# SH4_-_3_3V_LINEAR_REGULATOR.net
KiCad netlist of a schematic drawn in Altium Designer
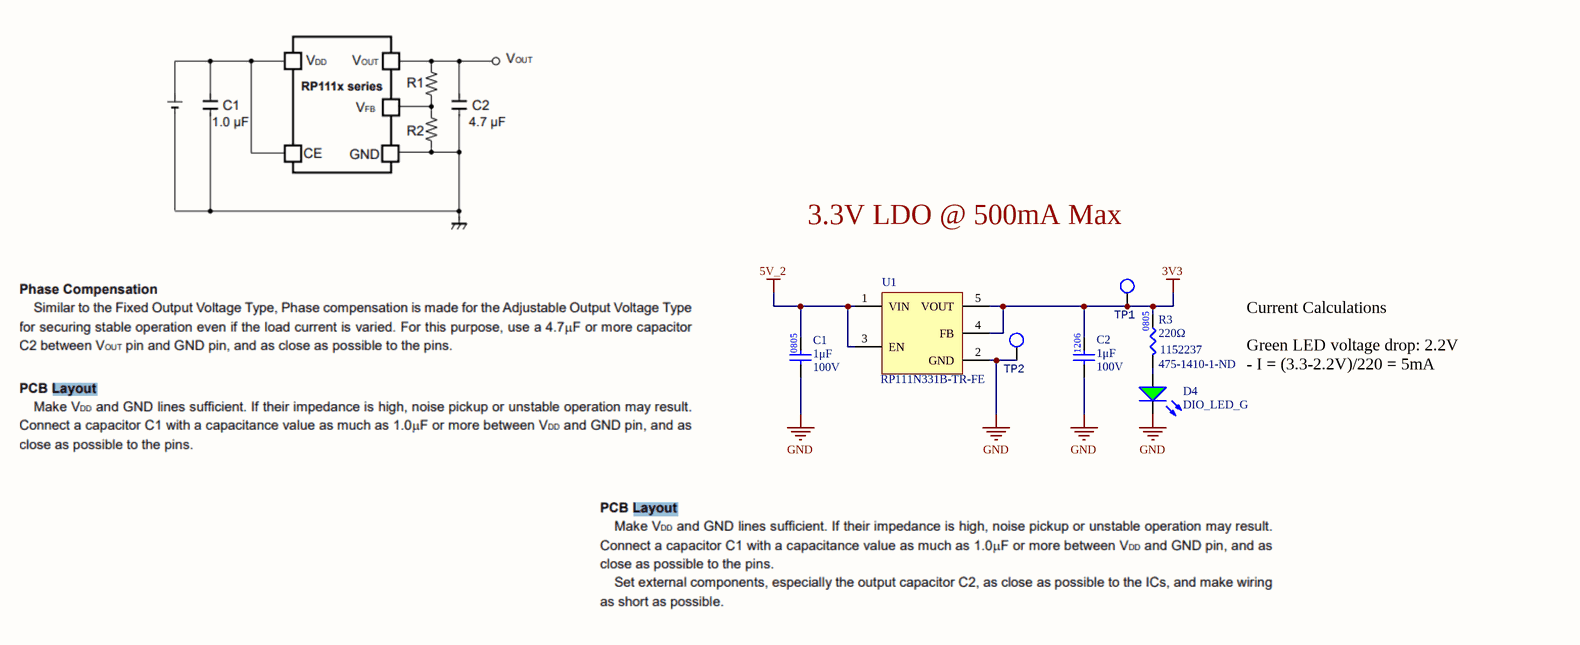
[diagram p0: SH4 - 3.3V LINEAR REGULATOR.SchDoc]

(export (version "E")
  (design (tool "Eeschema 10.0.6"))
  (components
    (comp (ref "C1")
      (value "1μF")
      (footprint "CAP0805")
      (description "CAP CER 1UF 100V X7S 0805")
      (fields (field (name "VOLTAGE RATING") "100V") (field (name "Comment") "CAP_1uF_100V_0805"))
      (libsource (lib "UWRT_Schematic_Library_2020") (part "CAP_1uF_100V_0805"))
    )
    (comp (ref "C2")
      (value "1μF")
      (footprint "CAPC3216X190X50NL20T25")
      (description "CAP CER 1UF 100V X7R 1206")
      (fields (field (name "VOLTAGE RATING") "100V") (field (name "Comment") "CAP_1uF_100V_1206"))
      (libsource (lib "UWRT_Schematic_Library_2020") (part "CAP_1uF_100V_1206"))
    )
    (comp (ref "D4")
      (value "DIO_LED_G")
      (footprint "LED_0805_GREEN")
      (description "LED GREEN DIFFUSED 0805 SMD")
      (fields
        (field (name "SUPPLIER PART NUMBER 1") "475-1410-1-ND")
        (field (name "SUPPLIER PART NUMBER 2") "1152237")
      )
      (libsource (lib "UWRT_Schematic_Library_2020") (part "DIO_LED_G"))
    )
    (comp (ref "R3")
      (value "220Ω")
      (footprint "RES0805")
      (description "RES 220 OHM 5% 1/2W 0805")
      (fields (field (name "LCSC PART #") "C17557") (field (name "Comment") "RES_220Ω_0805_5%"))
      (libsource (lib "UWRT_Schematic_Library_2020") (part "RES_220Ω_0805_5%"))
    )
    (comp (ref "TP1")
      (value "TESTPOINT_LOOP")
      (footprint "TESTPOINT_LOOP")
      (description "TESTPOINT THRUHOLE")
      (libsource (lib "UWRT_Schematic_Library_2020") (part "TESTPOINT_LOOP"))
    )
    (comp (ref "TP2")
      (value "TESTPOINT_LOOP")
      (footprint "TESTPOINT_LOOP")
      (description "TESTPOINT THRUHOLE")
      (libsource (lib "UWRT_Schematic_Library_2020") (part "TESTPOINT_LOOP"))
    )
    (comp (ref "U1")
      (value "LDO_3.3V_500mA")
      (footprint "SOT23-5")
      (description "IC REG LINEAR 3.3V 500MA SOT23-5")
      (fields (field (name "MANUFACTURER PART NUMBER 1") "RP111N331B-TR-FE"))
      (libsource (lib "UWRT_Schematic_Library_2020") (part "LDO_3.3V_500mA"))
    )
  )
  (nets
    (net (code "1") (name "3V3") (class "Default")
      (node (ref "C2") (pin "2") (pinfunction "2_2") (pintype "passive"))
      (node (ref "R3") (pin "2") (pinfunction "2_2") (pintype "passive"))
      (node (ref "TP1") (pin "1") (pintype "passive"))
      (node (ref "U1") (pin "4") (pinfunction "FB_4") (pintype "passive"))
      (node (ref "U1") (pin "5") (pinfunction "VOUT_5") (pintype "passive"))
    )
    (net (code "2") (name "5V_2") (class "Default")
      (node (ref "C1") (pin "2") (pinfunction "2_2") (pintype "passive"))
      (node (ref "U1") (pin "1") (pinfunction "VIN_1") (pintype "passive"))
      (node (ref "U1") (pin "3") (pinfunction "EN_3") (pintype "passive"))
    )
    (net (code "3") (name "GND") (class "Default")
      (node (ref "C1") (pin "1") (pinfunction "1_1") (pintype "passive"))
      (node (ref "C2") (pin "1") (pinfunction "1_1") (pintype "passive"))
      (node (ref "D4") (pin "2") (pinfunction "K_2") (pintype "passive"))
      (node (ref "TP2") (pin "1") (pintype "passive"))
      (node (ref "U1") (pin "2") (pinfunction "GND_2") (pintype "passive"))
    )
    (net (code "4") (name "Net-(D4-A)") (class "Default")
      (node (ref "D4") (pin "1") (pinfunction "A_1") (pintype "passive"))
      (node (ref "R3") (pin "1") (pinfunction "1_1") (pintype "passive"))
    )
  )
)
